# SMD.net
KiCad netlist of a schematic drawn in EAGLE
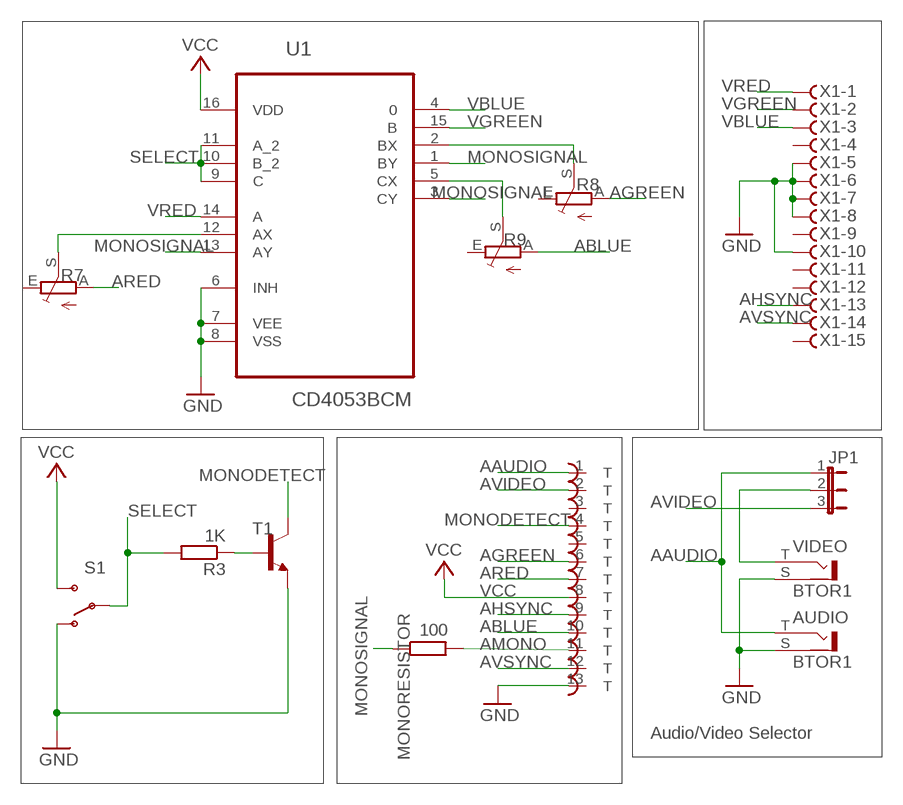
[diagram p0: schematic, sheet 1]

(export (version "E")
  (design (tool "Eeschema 10.0.6"))
  (components
    (comp (ref "ATARIOUT")
      (value "DIN13T")
      (footprint "eagle-import:ADADS")
      (libsource (lib "eagle-import") (part "DIN13T"))
    )
    (comp (ref "AUDIO")
      (value "BTOR1")
      (footprint "eagle-import:BTOR1")
      (libsource (lib "eagle-import") (part "BTOR1"))
    )
    (comp (ref "JP1")
      (value "JP2E")
      (footprint "eagle-import:JP2")
      (libsource (lib "eagle-import") (part "JP2E"))
    )
    (comp (ref "MONORESISTOR")
      (value "100")
      (footprint "eagle-import:0207_2V")
      (libsource (lib "eagle-import") (part "R-EU_0207/2V"))
    )
    (comp (ref "R3")
      (value "1K")
      (footprint "eagle-import:M1206")
      (libsource (lib "eagle-import") (part "R-EU_M1206"))
    )
    (comp (ref "R7")
      (value "TRIM_EU-CA6H")
      (footprint "eagle-import:CA6H")
      (libsource (lib "eagle-import") (part "TRIM_EU-CA6H"))
    )
    (comp (ref "R8")
      (value "TRIM_EU-CA6H")
      (footprint "eagle-import:CA6H")
      (libsource (lib "eagle-import") (part "TRIM_EU-CA6H"))
    )
    (comp (ref "R9")
      (value "TRIM_EU-CA6H")
      (footprint "eagle-import:CA6H")
      (libsource (lib "eagle-import") (part "TRIM_EU-CA6H"))
    )
    (comp (ref "S1")
      (value "SWITCH-SPDT-SMD-A")
      (footprint "eagle-import:SWITCH-SPST-SMD-A")
      (libsource (lib "eagle-import") (part "SWITCH-SPDT-SMD-A"))
    )
    (comp (ref "T1")
      (value "MMBT3904LT1-NPN-SOT23-BEC")
      (footprint "eagle-import:SOT23-BEC")
      (libsource (lib "eagle-import") (part "-NPN-SOT23-BECMMBT3904LT1"))
    )
    (comp (ref "U1")
      (value "CD4053BCM")
      (footprint "eagle-import:SOIC127P600X175-16N")
      (libsource (lib "eagle-import") (part "CD4053BCM"))
    )
    (comp (ref "VIDEO")
      (value "BTOR1")
      (footprint "eagle-import:BTOR1")
      (libsource (lib "eagle-import") (part "BTOR1"))
    )
    (comp (ref "X1")
      (value "F15HDVS")
      (footprint "eagle-import:HDF15V")
      (libsource (lib "eagle-import") (part "F15?SHDV"))
    )
  )
  (nets
    (net (code "1") (name "/AAUDIO") (class "Default")
      (node (ref "ATARIOUT") (pin "1") (pinfunction "T_1") (pintype "passive"))
      (node (ref "AUDIO") (pin "T") (pinfunction "1_T") (pintype "passive"))
      (node (ref "JP1") (pin "1") (pinfunction "1_1") (pintype "passive"))
    )
    (net (code "2") (name "/ABLUE") (class "Default")
      (node (ref "ATARIOUT") (pin "10") (pinfunction "T_10") (pintype "passive"))
      (node (ref "R9") (pin "A") (pinfunction "A_A") (pintype "passive"))
    )
    (net (code "3") (name "/AGREEN") (class "Default")
      (node (ref "ATARIOUT") (pin "6") (pinfunction "T_6") (pintype "passive"))
      (node (ref "R8") (pin "A") (pinfunction "A_A") (pintype "passive"))
    )
    (net (code "4") (name "/AHSYNC") (class "Default")
      (node (ref "ATARIOUT") (pin "9") (pinfunction "T_9") (pintype "passive"))
      (node (ref "X1") (pin "13") (pinfunction "F_13") (pintype "passive"))
    )
    (net (code "5") (name "/AMONO") (class "Default")
      (node (ref "ATARIOUT") (pin "11") (pinfunction "T_11") (pintype "passive"))
      (node (ref "MONORESISTOR") (pin "2") (pinfunction "2_2") (pintype "passive"))
    )
    (net (code "6") (name "/ARED") (class "Default")
      (node (ref "ATARIOUT") (pin "7") (pinfunction "T_7") (pintype "passive"))
      (node (ref "R7") (pin "A") (pinfunction "A_A") (pintype "passive"))
    )
    (net (code "7") (name "/AVIDEO") (class "Default")
      (node (ref "ATARIOUT") (pin "2") (pinfunction "T_2") (pintype "passive"))
      (node (ref "JP1") (pin "3") (pinfunction "3_3") (pintype "passive"))
    )
    (net (code "8") (name "/AVSYNC") (class "Default")
      (node (ref "ATARIOUT") (pin "12") (pinfunction "T_12") (pintype "passive"))
      (node (ref "X1") (pin "14") (pinfunction "F_14") (pintype "passive"))
    )
    (net (code "9") (name "/MONODETECT") (class "Default")
      (node (ref "ATARIOUT") (pin "4") (pinfunction "T_4") (pintype "passive"))
      (node (ref "T1") (pin "C") (pinfunction "C_C") (pintype "passive"))
    )
    (net (code "10") (name "/MONOSIGNAL") (class "Default")
      (node (ref "MONORESISTOR") (pin "1") (pinfunction "1_1") (pintype "passive"))
      (node (ref "U1") (pin "1") (pinfunction "BY_1") (pintype "bidirectional"))
      (node (ref "U1") (pin "13") (pinfunction "AY_13") (pintype "bidirectional"))
      (node (ref "U1") (pin "3") (pinfunction "CY_3") (pintype "bidirectional"))
    )
    (net (code "11") (name "/SELECT") (class "Default")
      (node (ref "R3") (pin "2") (pinfunction "2_2") (pintype "passive"))
      (node (ref "S1") (pin "2") (pinfunction "P_2") (pintype "passive"))
      (node (ref "U1") (pin "10") (pinfunction "B_2_10") (pintype "input"))
      (node (ref "U1") (pin "11") (pinfunction "A_2_11") (pintype "input"))
      (node (ref "U1") (pin "9") (pinfunction "C_9") (pintype "input"))
    )
    (net (code "12") (name "/VBLUE") (class "Default")
      (node (ref "U1") (pin "4") (pinfunction "0_4") (pintype "bidirectional"))
      (node (ref "X1") (pin "3") (pinfunction "F_3") (pintype "passive"))
    )
    (net (code "13") (name "/VGREEN") (class "Default")
      (node (ref "U1") (pin "15") (pinfunction "B_15") (pintype "bidirectional"))
      (node (ref "X1") (pin "2") (pinfunction "F_2") (pintype "passive"))
    )
    (net (code "14") (name "/VRED") (class "Default")
      (node (ref "U1") (pin "14") (pinfunction "A_14") (pintype "bidirectional"))
      (node (ref "X1") (pin "1") (pinfunction "F_1") (pintype "passive"))
    )
    (net (code "15") (name "GND") (class "Default")
      (node (ref "ATARIOUT") (pin "13") (pinfunction "T_13") (pintype "passive"))
      (node (ref "AUDIO") (pin "S") (pinfunction "2_S") (pintype "passive"))
      (node (ref "S1") (pin "1") (pinfunction "O_1") (pintype "passive"))
      (node (ref "T1") (pin "E") (pinfunction "E_E") (pintype "passive"))
      (node (ref "U1") (pin "6") (pinfunction "INH_6") (pintype "input"))
      (node (ref "U1") (pin "7") (pinfunction "VEE_7") (pintype "passive"))
      (node (ref "U1") (pin "8") (pinfunction "VSS_8") (pintype "power_in"))
      (node (ref "VIDEO") (pin "S") (pinfunction "2_S") (pintype "passive"))
      (node (ref "X1") (pin "10") (pinfunction "F_10") (pintype "passive"))
      (node (ref "X1") (pin "5") (pinfunction "F_5") (pintype "passive"))
      (node (ref "X1") (pin "6") (pinfunction "F_6") (pintype "passive"))
      (node (ref "X1") (pin "7") (pinfunction "F_7") (pintype "passive"))
      (node (ref "X1") (pin "8") (pinfunction "F_8") (pintype "passive"))
    )
    (net (code "16") (name "Net-(R3-Pad1)") (class "Default")
      (node (ref "R3") (pin "1") (pinfunction "1_1") (pintype "passive"))
      (node (ref "T1") (pin "B") (pinfunction "B_B") (pintype "passive"))
    )
    (net (code "17") (name "Net-(U1-AX)") (class "Default")
      (node (ref "R7") (pin "S") (pinfunction "S_S") (pintype "passive"))
      (node (ref "U1") (pin "12") (pinfunction "AX_12") (pintype "bidirectional"))
    )
    (net (code "18") (name "Net-(U1-BX)") (class "Default")
      (node (ref "R8") (pin "S") (pinfunction "S_S") (pintype "passive"))
      (node (ref "U1") (pin "2") (pinfunction "BX_2") (pintype "bidirectional"))
    )
    (net (code "19") (name "Net-(U1-CX)") (class "Default")
      (node (ref "R9") (pin "S") (pinfunction "S_S") (pintype "passive"))
      (node (ref "U1") (pin "5") (pinfunction "CX_5") (pintype "bidirectional"))
    )
    (net (code "20") (name "Net-(VIDEO-1)") (class "Default")
      (node (ref "JP1") (pin "2") (pinfunction "2_2") (pintype "passive"))
      (node (ref "VIDEO") (pin "T") (pinfunction "1_T") (pintype "passive"))
    )
    (net (code "21") (name "VCC") (class "Default")
      (node (ref "ATARIOUT") (pin "8") (pinfunction "T_8") (pintype "passive"))
      (node (ref "S1") (pin "3") (pinfunction "S_3") (pintype "passive"))
      (node (ref "U1") (pin "16") (pinfunction "VDD_16") (pintype "power_in"))
    )
    (net (code "22") (name "unconnected-(ATARIOUTG-T-Pad3)") (class "Default")
      (node (ref "ATARIOUT") (pin "3") (pinfunction "T_3") (pintype "passive"))
    )
    (net (code "23") (name "unconnected-(ATARIOUTI-T-Pad5)") (class "Default")
      (node (ref "ATARIOUT") (pin "5") (pinfunction "T_5") (pintype "passive"))
    )
    (net (code "24") (name "unconnected-(AUDIO-2-PadS@1)") (class "Default")
      (node (ref "AUDIO") (pin "S@1") (pinfunction "2_S@1") (pintype "passive"))
    )
    (net (code "25") (name "unconnected-(AUDIO-2-PadS@2)") (class "Default")
      (node (ref "AUDIO") (pin "S@2") (pinfunction "2_S@2") (pintype "passive"))
    )
    (net (code "26") (name "unconnected-(AUDIO-2-PadS@3)") (class "Default")
      (node (ref "AUDIO") (pin "S@3") (pinfunction "2_S@3") (pintype "passive"))
    )
    (net (code "27") (name "unconnected-(R7-PadE)") (class "Default")
      (node (ref "R7") (pin "E") (pinfunction "E_E") (pintype "passive"))
    )
    (net (code "28") (name "unconnected-(R8-PadE)") (class "Default")
      (node (ref "R8") (pin "E") (pinfunction "E_E") (pintype "passive"))
    )
    (net (code "29") (name "unconnected-(R9-PadE)") (class "Default")
      (node (ref "R9") (pin "E") (pinfunction "E_E") (pintype "passive"))
    )
    (net (code "30") (name "unconnected-(VIDEO-2-PadS@1)") (class "Default")
      (node (ref "VIDEO") (pin "S@1") (pinfunction "2_S@1") (pintype "passive"))
    )
    (net (code "31") (name "unconnected-(VIDEO-2-PadS@2)") (class "Default")
      (node (ref "VIDEO") (pin "S@2") (pinfunction "2_S@2") (pintype "passive"))
    )
    (net (code "32") (name "unconnected-(VIDEO-2-PadS@3)") (class "Default")
      (node (ref "VIDEO") (pin "S@3") (pinfunction "2_S@3") (pintype "passive"))
    )
    (net (code "33") (name "unconnected-(X1C-F-Pad11)") (class "Default")
      (node (ref "X1") (pin "11") (pinfunction "F_11") (pintype "passive"))
    )
    (net (code "34") (name "unconnected-(X1D-F-Pad12)") (class "Default")
      (node (ref "X1") (pin "12") (pinfunction "F_12") (pintype "passive"))
    )
    (net (code "35") (name "unconnected-(X1G-F-Pad15)") (class "Default")
      (node (ref "X1") (pin "15") (pinfunction "F_15") (pintype "passive"))
    )
    (net (code "36") (name "unconnected-(X1J-F-Pad4)") (class "Default")
      (node (ref "X1") (pin "4") (pinfunction "F_4") (pintype "passive"))
    )
    (net (code "37") (name "unconnected-(X1O-F-Pad9)") (class "Default")
      (node (ref "X1") (pin "9") (pinfunction "F_9") (pintype "passive"))
    )
  )
)
